# 12V_Buck_For_Rest.net
KiCad netlist of a schematic drawn in Altium Designer
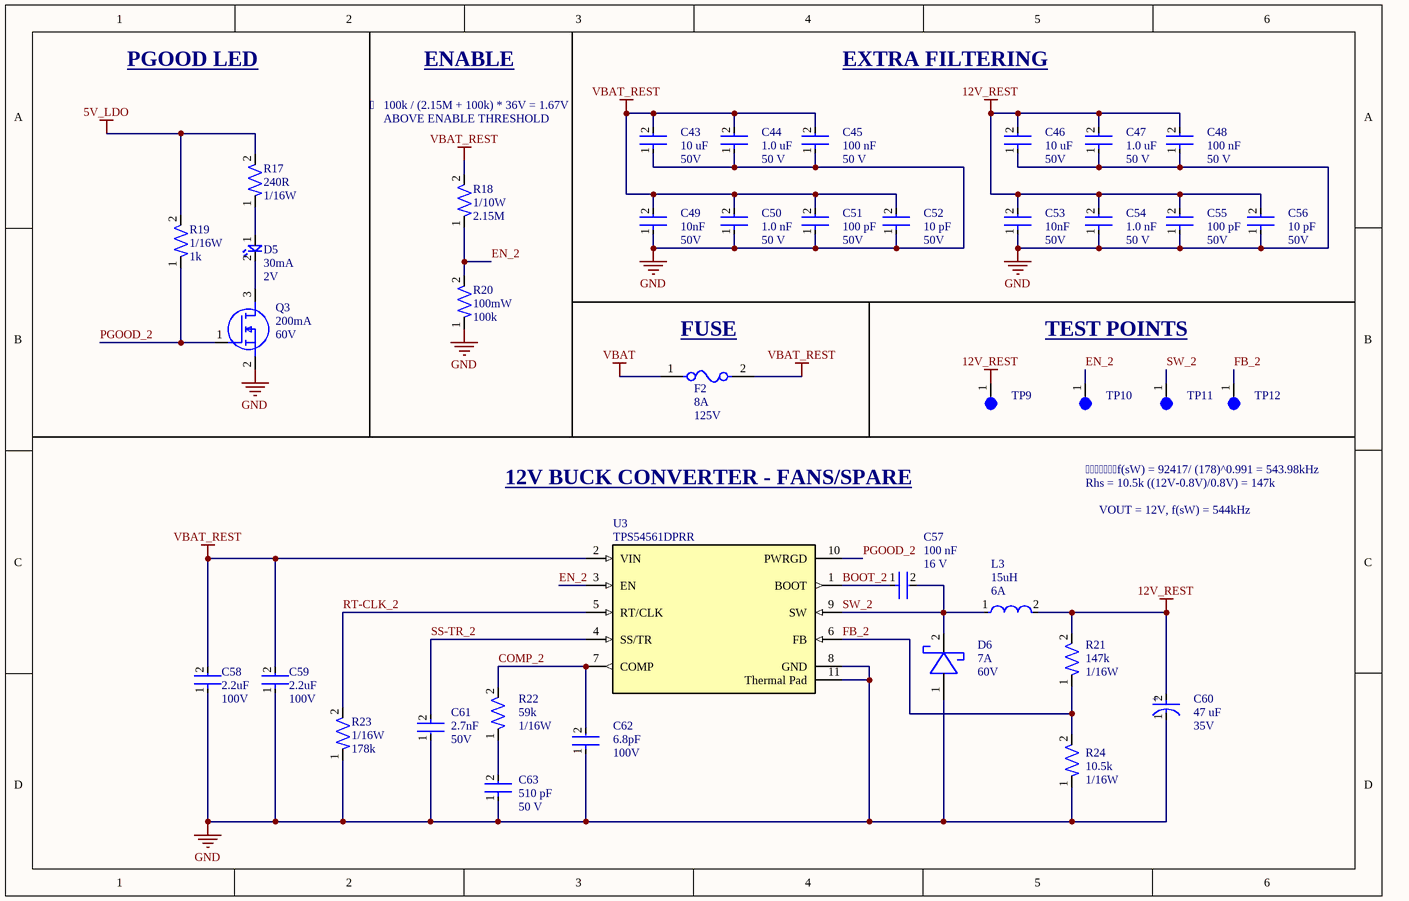
[diagram p0: 12V_Buck_For_Rest.SchDoc]

(export (version "E")
  (design (tool "Eeschema 10.0.6"))
  (components
    (comp (ref "C43")
      (value "CL32B106KBJNNNE")
      (footprint "CAP-1210")
      (description "CAP CER 10UF 50V X7R 1210")
      (fields (field (name "VOLTAGE") "50V") (field (name "CAPACITANCE") "10 uF"))
      (libsource (lib "JLC_25") (part "CAP-10U-0002"))
    )
    (comp (ref "C44")
      (value "CC0805KKX7R9BB105")
      (footprint "CAP-0805")
      (description "CAP CER 1UF 50V X7R 0805")
      (fields (field (name "VOLTAGE") "50 V") (field (name "CAPACITANCE") "1.0 uF"))
      (libsource (lib "JLC_25") (part "CAP-1U-0001"))
    )
    (comp (ref "C45")
      (value "CC0805KRX7R9BB104")
      (footprint "CAP-0805")
      (description "CAP CER 0.1UF 50V X7R 0805")
      (fields (field (name "VOLTAGE RATING") "50 V") (field (name "CAPACITANCE") "100 nF"))
      (libsource (lib "JLC_25") (part "CAP-0.1U-0002"))
    )
    (comp (ref "C46")
      (value "CL32B106KBJNNNE")
      (footprint "CAP-1210")
      (description "CAP CER 10UF 50V X7R 1210")
      (fields (field (name "VOLTAGE") "50V") (field (name "CAPACITANCE") "10 uF"))
      (libsource (lib "JLC_25") (part "CAP-10U-0002"))
    )
    (comp (ref "C47")
      (value "CC0805KKX7R9BB105")
      (footprint "CAP-0805")
      (description "CAP CER 1UF 50V X7R 0805")
      (fields (field (name "VOLTAGE") "50 V") (field (name "CAPACITANCE") "1.0 uF"))
      (libsource (lib "JLC_25") (part "CAP-1U-0001"))
    )
    (comp (ref "C48")
      (value "CC0805KRX7R9BB104")
      (footprint "CAP-0805")
      (description "CAP CER 0.1UF 50V X7R 0805")
      (fields (field (name "VOLTAGE RATING") "50 V") (field (name "CAPACITANCE") "100 nF"))
      (libsource (lib "JLC_25") (part "CAP-0.1U-0002"))
    )
    (comp (ref "C49")
      (value "GRM2195C1H103JA01D")
      (footprint "CAP-0805")
      (description "CAP CER 10000PF 50V C0G/NP0 0805")
      (fields (field (name "VOLTAGE") "50V") (field (name "CAPACITANCE") "10nF"))
      (libsource (lib "JLC_25") (part "CAP-10N-0001"))
    )
    (comp (ref "C50")
      (value "CC0402KRX7R9BB102")
      (footprint "CAP-0402")
      (description "CAP CER 1000PF 50V X7R 0402")
      (fields (field (name "VOLTAGE") "50 V") (field (name "CAPACITANCE") "1.0 nF"))
      (libsource (lib "JLC_25") (part "CAP-1N-0001"))
    )
    (comp (ref "C51")
      (value "CC0402JRNPO9BN101")
      (footprint "CAP-0402")
      (description "CAP CER 100PF 50V C0G/NPO 0402")
      (fields (field (name "CAPACITANCE") "100 pF") (field (name "VOLTAGE") "50V"))
      (libsource (lib "JLC_25") (part "CAP-100P-0001"))
    )
    (comp (ref "C52")
      (value "CC0402JRNPO9BN100")
      (footprint "CAP-0402")
      (description "CAP CER 10PF 50V C0G/NPO 0402")
      (fields (field (name "CAPACITANCE") "10 pF") (field (name "VOLTAGE") "50V"))
      (libsource (lib "JLC_25") (part "CAP-10P-0001"))
    )
    (comp (ref "C53")
      (value "GRM2195C1H103JA01D")
      (footprint "CAP-0805")
      (description "CAP CER 10000PF 50V C0G/NP0 0805")
      (fields (field (name "VOLTAGE") "50V") (field (name "CAPACITANCE") "10nF"))
      (libsource (lib "JLC_25") (part "CAP-10N-0001"))
    )
    (comp (ref "C54")
      (value "CC0402KRX7R9BB102")
      (footprint "CAP-0402")
      (description "CAP CER 1000PF 50V X7R 0402")
      (fields (field (name "VOLTAGE") "50 V") (field (name "CAPACITANCE") "1.0 nF"))
      (libsource (lib "JLC_25") (part "CAP-1N-0001"))
    )
    (comp (ref "C55")
      (value "CC0402JRNPO9BN101")
      (footprint "CAP-0402")
      (description "CAP CER 100PF 50V C0G/NPO 0402")
      (fields (field (name "CAPACITANCE") "100 pF") (field (name "VOLTAGE") "50V"))
      (libsource (lib "JLC_25") (part "CAP-100P-0001"))
    )
    (comp (ref "C56")
      (value "CC0402JRNPO9BN100")
      (footprint "CAP-0402")
      (description "CAP CER 10PF 50V C0G/NPO 0402")
      (fields (field (name "CAPACITANCE") "10 pF") (field (name "VOLTAGE") "50V"))
      (libsource (lib "JLC_25") (part "CAP-10P-0001"))
    )
    (comp (ref "C57")
      (value "CC0402KRX7R7BB104")
      (footprint "CAP-0402")
      (description "CAP CER 0.1UF 16V X7R 0402")
      (fields (field (name "VOLTAGE RATING") "16 V") (field (name "CAPACITANCE") "100 nF"))
      (libsource (lib "JLC_25") (part "CAP-0.1U-0001"))
    )
    (comp (ref "C58")
      (value "CC1206KKX7R0BB225")
      (footprint "CAP-1206")
      (description "CAP CER 2.2UF 100V X7R 1206")
      (fields (field (name "CAPACITANCE") "2.2uF") (field (name "VOLTAGE") "100V"))
      (libsource (lib "JLC_25") (part "CAP-2.2U-0001"))
    )
    (comp (ref "C59")
      (value "CC1206KKX7R0BB225")
      (footprint "CAP-1206")
      (description "CAP CER 2.2UF 100V X7R 1206")
      (fields (field (name "CAPACITANCE") "2.2uF") (field (name "VOLTAGE") "100V"))
      (libsource (lib "JLC_25") (part "CAP-2.2U-0001"))
    )
    (comp (ref "C60")
      (value "EEH-ZC1V470P")
      (footprint "CAP_EEHZC1V470P")
      (description "47 µF 35 V Aluminum - Polymer Capacitors Radial, Can - SMD 60mOhm 4000 Hrs @ 125°C")
      (fields (field (name "VOLTAGE") "35V") (field (name "CAPACITANCE") "47 uF"))
      (libsource (lib "JLC_25") (part "CAP-47U-0003"))
    )
    (comp (ref "C61")
      (value "GRM2165C1H272JA01D")
      (footprint "CAP-0805")
      (description "CAP CER 2700PF 50V C0G/NP0 0805")
      (fields (field (name "VOLTAGE") "50V") (field (name "CAPACITANCE") "2.7nF"))
      (libsource (lib "JLC_25") (part "CAP-2.7N-0001"))
    )
    (comp (ref "C62")
      (value "CC0603CRNPO0BN6R8")
      (footprint "CAP-0603")
      (description "CAP CER 6.8PF 100V C0G/NPO 0603")
      (fields (field (name "VOLTAGE") "100V") (field (name "CAPACITANCE") "6.8pF"))
      (libsource (lib "JLC_25") (part "CAP-6.8P-0001"))
    )
    (comp (ref "C63")
      (value "0402N511J500CT")
      (footprint "CAP-0402")
      (description "CAP CER 510PF 50V C0G/NP0 0402")
      (fields (field (name "VOLTAGE") "50 V") (field (name "CAPACITANCE") "510 pF"))
      (libsource (lib "JLC_25") (part "CAP-510P-0001"))
    )
    (comp (ref "D5")
      (value "BL-HKC36G-AV-TRB")
      (footprint "LED-0603")
      (description "LED YELLOW CLEAR 0603 SMD")
      (fields (field (name "FORWARD CURRENT") "30mA") (field (name "FORWARD VOLTAGE") "2V"))
      (libsource (lib "JLC_25") (part "LED-0001"))
    )
    (comp (ref "D6")
      (value "PDS760-13")
      (footprint "DO-POWERDI5")
      (description "DIODE SCHOTTKY 60V 7A POWERDI5")
      (fields (field (name "FORWARD CURRENT") "7A") (field (name "REVERSE VOLTAGE (DC)") "60V"))
      (libsource (lib "JLC_25") (part "DIO-SCHOTTKY-0001"))
    )
    (comp (ref "F2")
      (value "01550900M")
      (footprint "FUSE-0001")
      (description "FUSE BLOK CARTRIDGE 125V 10A SMD")
      (fields (field (name "FUSE CURRENT") "8A") (field (name "VOLTAGE RATING") "125V"))
      (libsource (lib "JLC_25") (part "FUSE-0001"))
    )
    (comp (ref "L3")
      (value "CSAD1010-150M")
      (footprint "IND-15U-0002")
      (description "SMD MOLDING POWER CHOKE")
      (fields (field (name "INDUCTANCE") "15uH") (field (name "CURRENT RATING") "6A"))
      (libsource (lib "JLC_25") (part "IND-15U-0002-NoJLC"))
    )
    (comp (ref "Q3")
      (value "T2N7002AK,LM")
      (footprint "IC-SOT23-3")
      (description "MOSFET N-CH 60V 200MA SOT23")
      (fields (field (name "CONTINUOUS CURRENT") "200mA") (field (name "VOLTAGE") "60V"))
      (libsource (lib "JLC_25") (part "NMOS-200MA-0001"))
    )
    (comp (ref "R17")
      (value "RC0402FR-07240RL")
      (footprint "RES-0402")
      (description "240R 0.063W 1% 0402 (1005 Metric)  SMD")
      (fields
        (field (name "TOLERANCE") "1%")
        (field (name "RESISTANCE") "240R")
        (field (name "POWER") "1/16W")
      )
      (libsource (lib "JLC_25") (part "RES-240-0001"))
    )
    (comp (ref "R18")
      (value "RC0603FR-072M15L")
      (footprint "RES-0603")
      (description "RES SMD 2.15M OHM 1% 1/10W 0603")
      (fields
        (field (name "TOLERANCE") "1%")
        (field (name "POWER") "1/10W")
        (field (name "RESISTANCE") "2.15M")
      )
      (libsource (lib "JLC_25") (part "RES-2.15M-0001"))
    )
    (comp (ref "R19")
      (value "RC0402FR-071KL")
      (footprint "RES-0402")
      (description "RES 1K OHM 1% 1/16W 0402")
      (fields (field (name "TOLERANCE") "1%") (field (name "POWER") "1/16W") (field (name "RESISTANCE") "1k"))
      (libsource (lib "JLC_25") (part "RES-1k-0001"))
    )
    (comp (ref "R20")
      (value "RC0603FR-07100KL")
      (footprint "RES-0603")
      (description "RES SMD 100K OHM 1% 1/10W 0603")
      (fields
        (field (name "TOLERANCE") "1%")
        (field (name "POWER") "100mW")
        (field (name "RESISTANCE") "100k")
      )
      (libsource (lib "JLC_25") (part "RES-100k-0001"))
    )
    (comp (ref "R21")
      (value "RC0402FR-07147KL")
      (footprint "RES-0402")
      (description "RES 147K OHM 1% 1/16W 0402")
      (fields
        (field (name "TOLERANCE") "1%")
        (field (name "POWER") "1/16W")
        (field (name "RESISTANCE") "147k")
      )
      (libsource (lib "JLC_25") (part "RES-147k-0001"))
    )
    (comp (ref "R22")
      (value "RC0402FR-0759KL")
      (footprint "RES-0402")
      (description "RES 59K OHM 1% 1/16W 0402")
      (fields
        (field (name "TOLERANCE") "1%")
        (field (name "POWER") "1/16W")
        (field (name "RESISTANCE") "59k")
      )
      (libsource (lib "JLC_25") (part "RES-59k-0001"))
    )
    (comp (ref "R23")
      (value "RTT021783FTH")
      (footprint "RES-0402")
      (description "62.5mW Thick Film Resistors 50V ±100ppm/℃ ±1% 178kΩ 0402 Chip Resistor - Surface Mount ROHS")
      (fields
        (field (name "TOLERANCE") "1%")
        (field (name "POWER") "1/16W")
        (field (name "RESISTANCE") "178k")
      )
      (libsource (lib "JLC_25") (part "RES-178k-0001_1"))
    )
    (comp (ref "R24")
      (value "RC0402FR-0710K5L")
      (footprint "RES-0402")
      (description "RES 10.5K OHM 1% 1/16W 0402")
      (fields
        (field (name "TOLERANCE") "1%")
        (field (name "POWER") "1/16W")
        (field (name "RESISTANCE") "10.5k")
      )
      (libsource (lib "JLC_25") (part "RES-10.5k-0001"))
    )
    (comp (ref "TP9")
      (value "5003")
      (footprint "TEST-POINT-0001")
      (description "Oranange PC Test Point, Miniature Phoisphor Bronze Silver Plating Through Hole Mounting Type")
      (libsource (lib "*") (part "TEST-POINT-0001"))
    )
    (comp (ref "TP10")
      (value "5003")
      (footprint "TEST-POINT-0001")
      (description "Oranange PC Test Point, Miniature Phoisphor Bronze Silver Plating Through Hole Mounting Type")
      (libsource (lib "*") (part "TEST-POINT-0001"))
    )
    (comp (ref "TP11")
      (value "5003")
      (footprint "TEST-POINT-0001")
      (description "Oranange PC Test Point, Miniature Phoisphor Bronze Silver Plating Through Hole Mounting Type")
      (libsource (lib "*") (part "TEST-POINT-0001"))
    )
    (comp (ref "TP12")
      (value "5003")
      (footprint "TEST-POINT-0001")
      (description "Oranange PC Test Point, Miniature Phoisphor Bronze Silver Plating Through Hole Mounting Type")
      (libsource (lib "*") (part "TEST-POINT-0001"))
    )
    (comp (ref "U3")
      (value "TPS54561DPRR")
      (footprint "IC-10WSON")
      (description "IC REG BUCK ADJ 5A 10WSON")
      (libsource (lib "JLC_25") (part "IC-BUCK-0001"))
    )
  )
  (nets
    (net (code "1") (name "/BOOT_2") (class "Default")
      (node (ref "C57") (pin "1") (pinfunction "1_1") (pintype "passive"))
      (node (ref "U3") (pin "1") (pinfunction "BOOT_1") (pintype "output"))
    )
    (net (code "2") (name "/COMP_2") (class "Default")
      (node (ref "C62") (pin "2") (pinfunction "2_2") (pintype "passive"))
      (node (ref "R22") (pin "2") (pinfunction "2_2") (pintype "passive"))
      (node (ref "U3") (pin "7") (pinfunction "COMP_7") (pintype "output"))
    )
    (net (code "3") (name "/EN_2") (class "Default")
      (node (ref "R18") (pin "1") (pinfunction "1_1") (pintype "passive"))
      (node (ref "R20") (pin "2") (pinfunction "2_2") (pintype "passive"))
      (node (ref "TP10") (pin "1") (pinfunction "0_1") (pintype "passive"))
      (node (ref "U3") (pin "3") (pinfunction "EN_3") (pintype "input"))
    )
    (net (code "4") (name "/FB_2") (class "Default")
      (node (ref "R21") (pin "1") (pinfunction "1_1") (pintype "passive"))
      (node (ref "R24") (pin "2") (pinfunction "2_2") (pintype "passive"))
      (node (ref "TP12") (pin "1") (pinfunction "0_1") (pintype "passive"))
      (node (ref "U3") (pin "6") (pinfunction "FB_6") (pintype "input"))
    )
    (net (code "5") (name "/PGOOD_2") (class "Default")
      (node (ref "Q3") (pin "1") (pinfunction "G_1") (pintype "passive"))
      (node (ref "R19") (pin "1") (pinfunction "1_1") (pintype "passive"))
      (node (ref "U3") (pin "10") (pinfunction "PWRGD_10") (pintype "open_collector"))
    )
    (net (code "6") (name "/RT-CLK_2") (class "Default")
      (node (ref "R23") (pin "2") (pinfunction "2_2") (pintype "passive"))
      (node (ref "U3") (pin "5") (pinfunction "RT/CLK_5") (pintype "input"))
    )
    (net (code "7") (name "/SS-TR_2") (class "Default")
      (node (ref "C61") (pin "2") (pinfunction "2_2") (pintype "passive"))
      (node (ref "U3") (pin "4") (pinfunction "SS/TR_4") (pintype "input"))
    )
    (net (code "8") (name "/SW_2") (class "Default")
      (node (ref "C57") (pin "2") (pinfunction "2_2") (pintype "passive"))
      (node (ref "D6") (pin "2") (pinfunction "ANODE_2") (pintype "passive"))
      (node (ref "L3") (pin "1") (pinfunction "1_1") (pintype "passive"))
      (node (ref "TP11") (pin "1") (pinfunction "0_1") (pintype "passive"))
      (node (ref "U3") (pin "9") (pinfunction "SW_9") (pintype "input"))
    )
    (net (code "9") (name "5V_LDO") (class "Default")
      (node (ref "R17") (pin "2") (pinfunction "2_2") (pintype "passive"))
      (node (ref "R19") (pin "2") (pinfunction "2_2") (pintype "passive"))
    )
    (net (code "10") (name "12V_REST") (class "Default")
      (node (ref "C46") (pin "2") (pinfunction "2_2") (pintype "passive"))
      (node (ref "C47") (pin "2") (pinfunction "2_2") (pintype "passive"))
      (node (ref "C48") (pin "2") (pinfunction "2_2") (pintype "passive"))
      (node (ref "C53") (pin "2") (pinfunction "2_2") (pintype "passive"))
      (node (ref "C54") (pin "2") (pinfunction "2_2") (pintype "passive"))
      (node (ref "C55") (pin "2") (pinfunction "2_2") (pintype "passive"))
      (node (ref "C56") (pin "2") (pinfunction "2_2") (pintype "passive"))
      (node (ref "C60") (pin "2") (pinfunction "A_2") (pintype "passive"))
      (node (ref "L3") (pin "2") (pinfunction "2_2") (pintype "passive"))
      (node (ref "R21") (pin "2") (pinfunction "2_2") (pintype "passive"))
      (node (ref "TP9") (pin "1") (pinfunction "0_1") (pintype "passive"))
    )
    (net (code "11") (name "GND") (class "Default")
      (node (ref "C43") (pin "1") (pinfunction "1_1") (pintype "passive"))
      (node (ref "C44") (pin "1") (pinfunction "1_1") (pintype "passive"))
      (node (ref "C45") (pin "1") (pinfunction "1_1") (pintype "passive"))
      (node (ref "C46") (pin "1") (pinfunction "1_1") (pintype "passive"))
      (node (ref "C47") (pin "1") (pinfunction "1_1") (pintype "passive"))
      (node (ref "C48") (pin "1") (pinfunction "1_1") (pintype "passive"))
      (node (ref "C49") (pin "1") (pinfunction "1_1") (pintype "passive"))
      (node (ref "C50") (pin "1") (pinfunction "1_1") (pintype "passive"))
      (node (ref "C51") (pin "1") (pinfunction "1_1") (pintype "passive"))
      (node (ref "C52") (pin "1") (pinfunction "1_1") (pintype "passive"))
      (node (ref "C53") (pin "1") (pinfunction "1_1") (pintype "passive"))
      (node (ref "C54") (pin "1") (pinfunction "1_1") (pintype "passive"))
      (node (ref "C55") (pin "1") (pinfunction "1_1") (pintype "passive"))
      (node (ref "C56") (pin "1") (pinfunction "1_1") (pintype "passive"))
      (node (ref "C58") (pin "1") (pinfunction "1_1") (pintype "passive"))
      (node (ref "C59") (pin "1") (pinfunction "1_1") (pintype "passive"))
      (node (ref "C60") (pin "1") (pinfunction "C_1") (pintype "passive"))
      (node (ref "C61") (pin "1") (pinfunction "1_1") (pintype "passive"))
      (node (ref "C62") (pin "1") (pinfunction "1_1") (pintype "passive"))
      (node (ref "C63") (pin "1") (pinfunction "1_1") (pintype "passive"))
      (node (ref "D6") (pin "1") (pinfunction "CATHODE_1") (pintype "passive"))
      (node (ref "Q3") (pin "2") (pinfunction "S_2") (pintype "passive"))
      (node (ref "R20") (pin "1") (pinfunction "1_1") (pintype "passive"))
      (node (ref "R23") (pin "1") (pinfunction "1_1") (pintype "passive"))
      (node (ref "R24") (pin "1") (pinfunction "1_1") (pintype "passive"))
      (node (ref "U3") (pin "11") (pinfunction "Thermal_Pad_11") (pintype "power_in"))
      (node (ref "U3") (pin "8") (pinfunction "GND_8") (pintype "power_in"))
    )
    (net (code "12") (name "Net-(C63-Pad2)") (class "Default")
      (node (ref "C63") (pin "2") (pinfunction "2_2") (pintype "passive"))
      (node (ref "R22") (pin "1") (pinfunction "1_1") (pintype "passive"))
    )
    (net (code "13") (name "Net-(D5-Pad1)") (class "Default")
      (node (ref "D5") (pin "1") (pinfunction "1_1") (pintype "passive"))
      (node (ref "R17") (pin "1") (pinfunction "1_1") (pintype "passive"))
    )
    (net (code "14") (name "Net-(Q3-D)") (class "Default")
      (node (ref "D5") (pin "2") (pinfunction "2_2") (pintype "passive"))
      (node (ref "Q3") (pin "3") (pinfunction "D_3") (pintype "passive"))
    )
    (net (code "15") (name "VBAT") (class "Default")
      (node (ref "F2") (pin "1") (pinfunction "1_1") (pintype "passive"))
    )
    (net (code "16") (name "VBAT_REST") (class "Default")
      (node (ref "C43") (pin "2") (pinfunction "2_2") (pintype "passive"))
      (node (ref "C44") (pin "2") (pinfunction "2_2") (pintype "passive"))
      (node (ref "C45") (pin "2") (pinfunction "2_2") (pintype "passive"))
      (node (ref "C49") (pin "2") (pinfunction "2_2") (pintype "passive"))
      (node (ref "C50") (pin "2") (pinfunction "2_2") (pintype "passive"))
      (node (ref "C51") (pin "2") (pinfunction "2_2") (pintype "passive"))
      (node (ref "C52") (pin "2") (pinfunction "2_2") (pintype "passive"))
      (node (ref "C58") (pin "2") (pinfunction "2_2") (pintype "passive"))
      (node (ref "C59") (pin "2") (pinfunction "2_2") (pintype "passive"))
      (node (ref "F2") (pin "2") (pinfunction "2_2") (pintype "passive"))
      (node (ref "R18") (pin "2") (pinfunction "2_2") (pintype "passive"))
      (node (ref "U3") (pin "2") (pinfunction "VIN_2") (pintype "input"))
    )
  )
)
